# CS_COMM.net
KiCad netlist of a schematic drawn in EAGLE
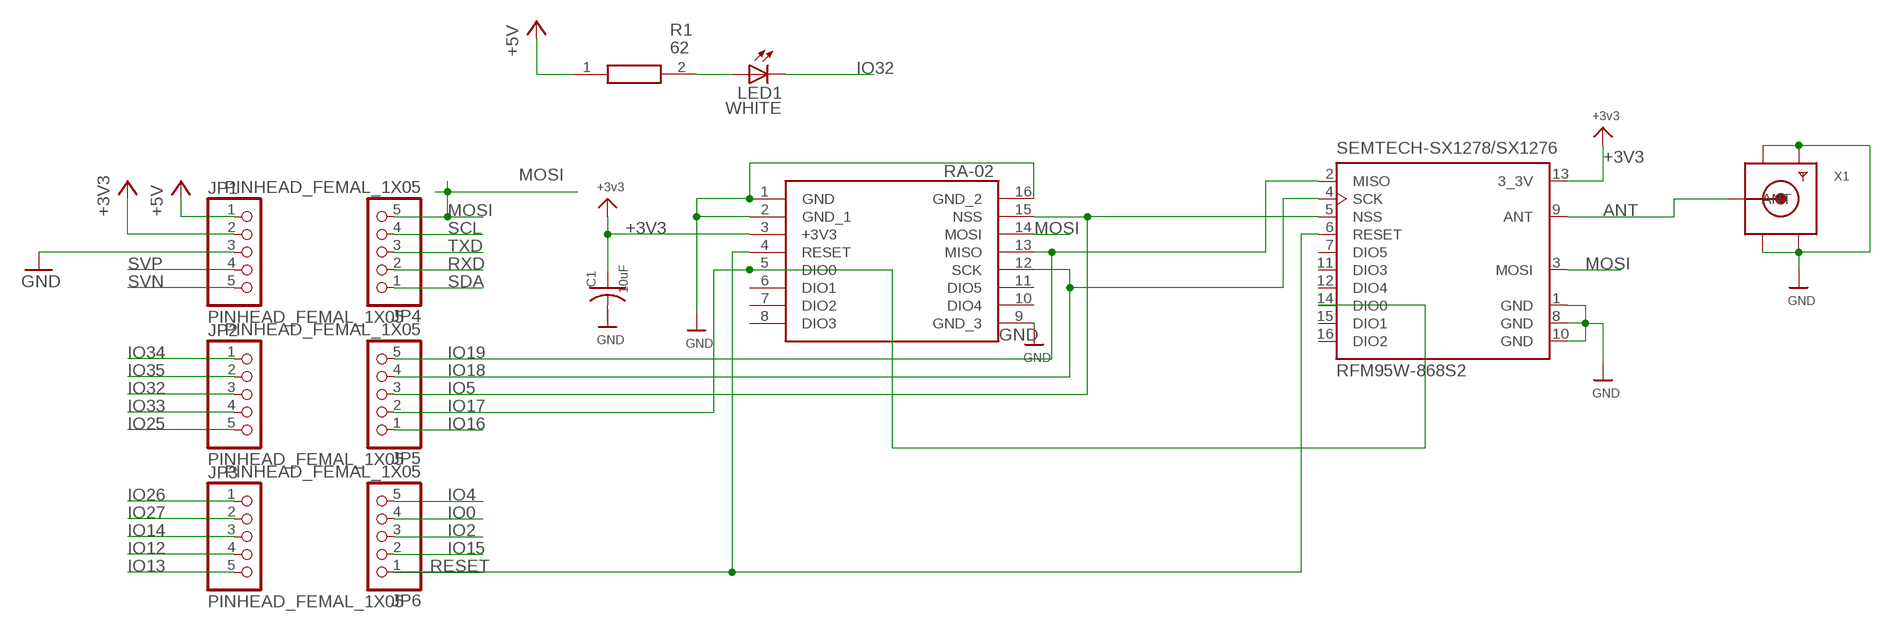
[diagram p0: schematic, sheet 1]

(export (version "E")
  (design (tool "Eeschema 10.0.6"))
  (components
    (comp (ref "AI-THINKER_RA-02")
      (value "RA-02SMD-16")
      (footprint "eagle-import:SON200P1600X1650X200-16")
      (libsource (lib "eagle-import") (part "RA-02SMD-16"))
    )
    (comp (ref "C1")
      (value "10uF")
      (footprint "eagle-import:C0805")
      (libsource (lib "eagle-import") (part "C-USC0805"))
    )
    (comp (ref "JP1")
      (value "PINHEAD_FEMAL_1X05")
      (footprint "eagle-import:1X05F")
      (libsource (lib "eagle-import") (part "PINHEAD_FEMAL_1X05"))
    )
    (comp (ref "JP2")
      (value "PINHEAD_FEMAL_1X05")
      (footprint "eagle-import:1X05F")
      (libsource (lib "eagle-import") (part "PINHEAD_FEMAL_1X05"))
    )
    (comp (ref "JP3")
      (value "PINHEAD_FEMAL_1X05")
      (footprint "eagle-import:1X05F")
      (libsource (lib "eagle-import") (part "PINHEAD_FEMAL_1X05"))
    )
    (comp (ref "JP4")
      (value "PINHEAD_FEMAL_1X05")
      (footprint "eagle-import:1X05F")
      (libsource (lib "eagle-import") (part "PINHEAD_FEMAL_1X05"))
    )
    (comp (ref "JP5")
      (value "PINHEAD_FEMAL_1X05")
      (footprint "eagle-import:1X05F")
      (libsource (lib "eagle-import") (part "PINHEAD_FEMAL_1X05"))
    )
    (comp (ref "JP6")
      (value "PINHEAD_FEMAL_1X05")
      (footprint "eagle-import:1X05F")
      (libsource (lib "eagle-import") (part "PINHEAD_FEMAL_1X05"))
    )
    (comp (ref "LED1")
      (value "WHITE")
      (footprint "eagle-import:CHIPLED_1206")
      (libsource (lib "eagle-import") (part "LEDCHIPLED_1206"))
    )
    (comp (ref "R1")
      (value "62")
      (footprint "eagle-import:RESC2012X60N")
      (fields
        (field (name "MANUFACTURER_PART_NUMBER") "ERA-6AED684V")
        (field (name "MOUSER_PART_NUMBER") "667-ERA-6AED684V")
      )
      (libsource (lib "eagle-import") (part "ERA-6AED684V"))
    )
    (comp (ref "SEMTECH-SX1278/SX1276")
      (value "RFM95W-868S2")
      (footprint "eagle-import:XCVR_RFM95W-868S2")
      (fields (field (name "DIGI-KEY_PART_NUMBER") "RFM95W-868S2-ND") (field (name "MF") "RF"))
      (libsource (lib "eagle-import") (part "RFM95W-868S2"))
    )
    (comp (ref "X1")
      (value "SMACONNECTOR")
      (footprint "eagle-import:SMA90_DIP")
      (libsource (lib "eagle-import") (part "SMACONNECTOR"))
    )
  )
  (nets
    (net (code "1") (name "+3V3") (class "Default")
      (node (ref "AI-THINKER_RA-02") (pin "3") (pinfunction "+3V3_3") (pintype "bidirectional"))
      (node (ref "C1") (pin "1") (pinfunction "1_1") (pintype "passive"))
      (node (ref "JP1") (pin "2") (pinfunction "2_2") (pintype "passive"))
      (node (ref "SEMTECH-SX1278/SX1276") (pin "13") (pinfunction "3_3V_13") (pintype "power_in"))
    )
    (net (code "2") (name "+5V") (class "Default")
      (node (ref "JP1") (pin "1") (pinfunction "1_1") (pintype "passive"))
      (node (ref "R1") (pin "1") (pinfunction "1_1") (pintype "bidirectional"))
    )
    (net (code "3") (name "/ANT") (class "Default")
      (node (ref "SEMTECH-SX1278/SX1276") (pin "9") (pinfunction "ANT_9") (pintype "passive"))
      (node (ref "X1") (pin "ANTENNA") (pinfunction "ANT_ANTENNA") (pintype "bidirectional"))
    )
    (net (code "4") (name "/IO0") (class "Default")
      (node (ref "JP6") (pin "4") (pinfunction "4_4") (pintype "passive"))
    )
    (net (code "5") (name "/IO2") (class "Default")
      (node (ref "JP6") (pin "3") (pinfunction "3_3") (pintype "passive"))
    )
    (net (code "6") (name "/IO4") (class "Default")
      (node (ref "JP6") (pin "5") (pinfunction "5_5") (pintype "passive"))
    )
    (net (code "7") (name "/IO5") (class "Default")
      (node (ref "AI-THINKER_RA-02") (pin "15") (pinfunction "NSS_15") (pintype "bidirectional"))
      (node (ref "JP5") (pin "3") (pinfunction "3_3") (pintype "passive"))
      (node (ref "SEMTECH-SX1278/SX1276") (pin "5") (pinfunction "NSS_5") (pintype "input"))
    )
    (net (code "8") (name "/IO12") (class "Default")
      (node (ref "JP3") (pin "4") (pinfunction "4_4") (pintype "passive"))
    )
    (net (code "9") (name "/IO13") (class "Default")
      (node (ref "JP3") (pin "5") (pinfunction "5_5") (pintype "passive"))
    )
    (net (code "10") (name "/IO14") (class "Default")
      (node (ref "JP3") (pin "3") (pinfunction "3_3") (pintype "passive"))
    )
    (net (code "11") (name "/IO15") (class "Default")
      (node (ref "JP6") (pin "2") (pinfunction "2_2") (pintype "passive"))
    )
    (net (code "12") (name "/IO16") (class "Default")
      (node (ref "JP5") (pin "1") (pinfunction "1_1") (pintype "passive"))
    )
    (net (code "13") (name "/IO17") (class "Default")
      (node (ref "AI-THINKER_RA-02") (pin "5") (pinfunction "DIO0_5") (pintype "bidirectional"))
      (node (ref "JP5") (pin "2") (pinfunction "2_2") (pintype "passive"))
      (node (ref "SEMTECH-SX1278/SX1276") (pin "14") (pinfunction "DIO0_14") (pintype "bidirectional"))
    )
    (net (code "14") (name "/IO18") (class "Default")
      (node (ref "AI-THINKER_RA-02") (pin "12") (pinfunction "SCK_12") (pintype "bidirectional"))
      (node (ref "JP5") (pin "4") (pinfunction "4_4") (pintype "passive"))
      (node (ref "SEMTECH-SX1278/SX1276") (pin "4") (pinfunction "SCK_4") (pintype "input"))
    )
    (net (code "15") (name "/IO19") (class "Default")
      (node (ref "AI-THINKER_RA-02") (pin "13") (pinfunction "MISO_13") (pintype "bidirectional"))
      (node (ref "JP5") (pin "5") (pinfunction "5_5") (pintype "passive"))
      (node (ref "SEMTECH-SX1278/SX1276") (pin "2") (pinfunction "MISO_2") (pintype "input"))
    )
    (net (code "16") (name "/IO25") (class "Default")
      (node (ref "JP2") (pin "5") (pinfunction "5_5") (pintype "passive"))
    )
    (net (code "17") (name "/IO26") (class "Default")
      (node (ref "JP3") (pin "1") (pinfunction "1_1") (pintype "passive"))
    )
    (net (code "18") (name "/IO27") (class "Default")
      (node (ref "JP3") (pin "2") (pinfunction "2_2") (pintype "passive"))
    )
    (net (code "19") (name "/IO32") (class "Default")
      (node (ref "JP2") (pin "3") (pinfunction "3_3") (pintype "passive"))
      (node (ref "LED1") (pin "C") (pinfunction "C_C") (pintype "passive"))
    )
    (net (code "20") (name "/IO33") (class "Default")
      (node (ref "JP2") (pin "4") (pinfunction "4_4") (pintype "passive"))
    )
    (net (code "21") (name "/IO34") (class "Default")
      (node (ref "JP2") (pin "1") (pinfunction "1_1") (pintype "passive"))
    )
    (net (code "22") (name "/IO35") (class "Default")
      (node (ref "JP2") (pin "2") (pinfunction "2_2") (pintype "passive"))
    )
    (net (code "23") (name "/MOSI") (class "Default")
      (node (ref "AI-THINKER_RA-02") (pin "14") (pinfunction "MOSI_14") (pintype "bidirectional"))
      (node (ref "JP4") (pin "5") (pinfunction "5_5") (pintype "passive"))
      (node (ref "SEMTECH-SX1278/SX1276") (pin "3") (pinfunction "MOSI_3") (pintype "output"))
    )
    (net (code "24") (name "/RESET") (class "Default")
      (node (ref "AI-THINKER_RA-02") (pin "4") (pinfunction "RESET_4") (pintype "bidirectional"))
      (node (ref "JP6") (pin "1") (pinfunction "1_1") (pintype "passive"))
      (node (ref "SEMTECH-SX1278/SX1276") (pin "6") (pinfunction "RESET_6") (pintype "bidirectional"))
    )
    (net (code "25") (name "/RXD") (class "Default")
      (node (ref "JP4") (pin "2") (pinfunction "2_2") (pintype "passive"))
    )
    (net (code "26") (name "/SCL") (class "Default")
      (node (ref "JP4") (pin "4") (pinfunction "4_4") (pintype "passive"))
    )
    (net (code "27") (name "/SDA") (class "Default")
      (node (ref "JP4") (pin "1") (pinfunction "1_1") (pintype "passive"))
    )
    (net (code "28") (name "/SVN") (class "Default")
      (node (ref "JP1") (pin "5") (pinfunction "5_5") (pintype "passive"))
    )
    (net (code "29") (name "/SVP") (class "Default")
      (node (ref "JP1") (pin "4") (pinfunction "4_4") (pintype "passive"))
    )
    (net (code "30") (name "/TXD") (class "Default")
      (node (ref "JP4") (pin "3") (pinfunction "3_3") (pintype "passive"))
    )
    (net (code "31") (name "GND") (class "Default")
      (node (ref "AI-THINKER_RA-02") (pin "1") (pinfunction "GND_1") (pintype "bidirectional"))
      (node (ref "AI-THINKER_RA-02") (pin "16") (pinfunction "GND_2_16") (pintype "bidirectional"))
      (node (ref "AI-THINKER_RA-02") (pin "2") (pinfunction "GND_1_2") (pintype "bidirectional"))
      (node (ref "AI-THINKER_RA-02") (pin "9") (pinfunction "GND_3_9") (pintype "bidirectional"))
      (node (ref "C1") (pin "2") (pinfunction "2_2") (pintype "passive"))
      (node (ref "JP1") (pin "3") (pinfunction "3_3") (pintype "passive"))
      (node (ref "SEMTECH-SX1278/SX1276") (pin "1") (pinfunction "GND_1") (pintype "power_in"))
      (node (ref "SEMTECH-SX1278/SX1276") (pin "10") (pinfunction "GND_10") (pintype "power_in"))
      (node (ref "SEMTECH-SX1278/SX1276") (pin "8") (pinfunction "GND_8") (pintype "power_in"))
      (node (ref "X1") (pin "GND1") (pinfunction "GND1_GND1") (pintype "power_in"))
      (node (ref "X1") (pin "GND2") (pinfunction "GND2_GND2") (pintype "power_in"))
      (node (ref "X1") (pin "GND3") (pinfunction "GND3_GND3") (pintype "power_in"))
      (node (ref "X1") (pin "GND4") (pinfunction "GND4_GND4") (pintype "power_in"))
    )
    (net (code "32") (name "Net-(LED1-PadA)") (class "Default")
      (node (ref "LED1") (pin "A") (pinfunction "A_A") (pintype "passive"))
      (node (ref "R1") (pin "2") (pinfunction "2_2") (pintype "bidirectional"))
    )
    (net (code "33") (name "unconnected-(AI-THINKER_RA-02-DIO1-Pad6)") (class "Default")
      (node (ref "AI-THINKER_RA-02") (pin "6") (pinfunction "DIO1_6") (pintype "bidirectional"))
    )
    (net (code "34") (name "unconnected-(AI-THINKER_RA-02-DIO2-Pad7)") (class "Default")
      (node (ref "AI-THINKER_RA-02") (pin "7") (pinfunction "DIO2_7") (pintype "bidirectional"))
    )
    (net (code "35") (name "unconnected-(AI-THINKER_RA-02-DIO3-Pad8)") (class "Default")
      (node (ref "AI-THINKER_RA-02") (pin "8") (pinfunction "DIO3_8") (pintype "bidirectional"))
    )
    (net (code "36") (name "unconnected-(AI-THINKER_RA-02-DIO4-Pad10)") (class "Default")
      (node (ref "AI-THINKER_RA-02") (pin "10") (pinfunction "DIO4_10") (pintype "bidirectional"))
    )
    (net (code "37") (name "unconnected-(AI-THINKER_RA-02-DIO5-Pad11)") (class "Default")
      (node (ref "AI-THINKER_RA-02") (pin "11") (pinfunction "DIO5_11") (pintype "bidirectional"))
    )
    (net (code "38") (name "unconnected-(SEMTECH-SX1278/SX1276-DIO1-Pad15)") (class "Default")
      (node (ref "SEMTECH-SX1278/SX1276") (pin "15") (pinfunction "DIO1_15") (pintype "bidirectional"))
    )
    (net (code "39") (name "unconnected-(SEMTECH-SX1278/SX1276-DIO2-Pad16)") (class "Default")
      (node (ref "SEMTECH-SX1278/SX1276") (pin "16") (pinfunction "DIO2_16") (pintype "bidirectional"))
    )
    (net (code "40") (name "unconnected-(SEMTECH-SX1278/SX1276-DIO3-Pad11)") (class "Default")
      (node (ref "SEMTECH-SX1278/SX1276") (pin "11") (pinfunction "DIO3_11") (pintype "bidirectional"))
    )
    (net (code "41") (name "unconnected-(SEMTECH-SX1278/SX1276-DIO4-Pad12)") (class "Default")
      (node (ref "SEMTECH-SX1278/SX1276") (pin "12") (pinfunction "DIO4_12") (pintype "bidirectional"))
    )
    (net (code "42") (name "unconnected-(SEMTECH-SX1278/SX1276-DIO5-Pad7)") (class "Default")
      (node (ref "SEMTECH-SX1278/SX1276") (pin "7") (pinfunction "DIO5_7") (pintype "bidirectional"))
    )
  )
)
